# ControlBrickLogic2_0.net
KiCad netlist of a schematic drawn in Altium Designer
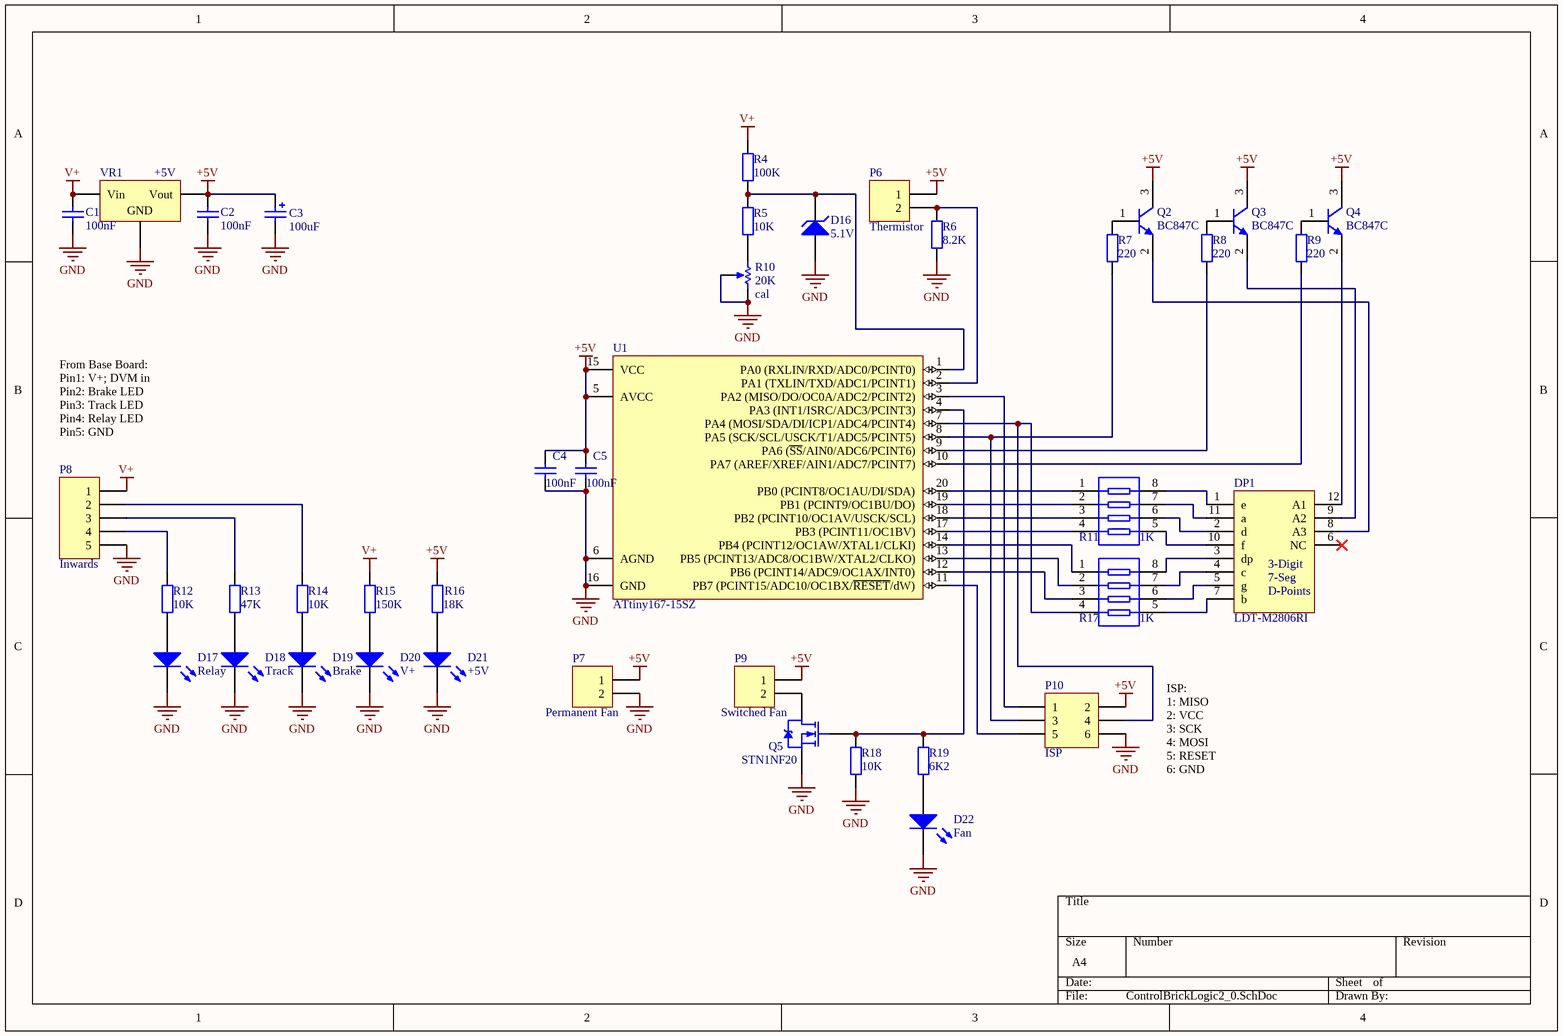
[diagram p0: ControlBrickLogic2_0.SchDoc]

(export (version "E")
  (design (tool "Eeschema 10.0.6"))
  (components
    (comp (ref "C1")
      (value "100nF")
      (footprint "1206")
      (description "Capacitor")
      (fields (field (name "Comment") "CapSMD") (field (name "PUBLISHER") "Altium Limited"))
      (libsource (lib "SpecificComponents") (part "CapSMD"))
    )
    (comp (ref "C2")
      (value "100nF")
      (footprint "1206")
      (description "Capacitor")
      (fields (field (name "Comment") "CapSMD") (field (name "PUBLISHER") "Altium Limited"))
      (libsource (lib "SpecificComponents") (part "CapSMD"))
    )
    (comp (ref "C3")
      (value "100uF")
      (footprint "SMDcap 5mm")
      (description "Polarized Capacitor (Axial)")
      (fields (field (name "Comment") "Supercap") (field (name "PUBLISHER") "Altium Limited"))
      (libsource (lib "Miscellaneous Devices") (part "Cap Pol2"))
    )
    (comp (ref "C4")
      (value "100nF")
      (footprint "1206")
      (description "Capacitor")
      (fields (field (name "Comment") "CapSMD") (field (name "PUBLISHER") "Altium Limited"))
      (libsource (lib "SpecificComponents") (part "CapSMD"))
    )
    (comp (ref "C5")
      (value "100nF")
      (footprint "1206")
      (description "Capacitor")
      (fields (field (name "Comment") "CapSMD") (field (name "PUBLISHER") "Altium Limited"))
      (libsource (lib "SpecificComponents") (part "CapSMD"))
    )
    (comp (ref "D16")
      (value "5.1V")
      (footprint "MiniMELF")
      (description "Zener Diode")
      (fields (field (name "PUBLISHER") "Altium Limited"))
      (libsource (lib "SpecificComponents") (part "D Zener"))
    )
    (comp (ref "D17")
      (value "Relay")
      (footprint "LED 2.54")
      (description "Typical RED GaAs LED")
      (fields (field (name "PUBLISHER") "Altium Limited"))
      (libsource (lib "Miscellaneous Devices") (part "LED1"))
    )
    (comp (ref "D18")
      (value "Track")
      (footprint "LED 2.54")
      (description "Typical RED GaAs LED")
      (fields (field (name "PUBLISHER") "Altium Limited"))
      (libsource (lib "Miscellaneous Devices") (part "LED1"))
    )
    (comp (ref "D19")
      (value "Brake")
      (footprint "LED 2.54")
      (description "Typical RED GaAs LED")
      (fields (field (name "PUBLISHER") "Altium Limited"))
      (libsource (lib "Miscellaneous Devices") (part "LED1"))
    )
    (comp (ref "D20")
      (value "V+")
      (footprint "LED 2.54")
      (description "Typical RED GaAs LED")
      (fields (field (name "PUBLISHER") "Altium Limited"))
      (libsource (lib "Miscellaneous Devices") (part "LED1"))
    )
    (comp (ref "D21")
      (value "+5V")
      (footprint "LED 2.54")
      (description "Typical RED GaAs LED")
      (fields (field (name "PUBLISHER") "Altium Limited"))
      (libsource (lib "Miscellaneous Devices") (part "LED1"))
    )
    (comp (ref "D22")
      (value "Fan")
      (footprint "LED 2.54")
      (description "Typical RED GaAs LED")
      (fields (field (name "PUBLISHER") "Altium Limited"))
      (libsource (lib "Miscellaneous Devices") (part "LED1"))
    )
    (comp (ref "DP1")
      (value "LDT-M2806RI")
      (footprint "LDT-M2806RI")
      (libsource (lib "SpecificComponents") (part "7Seg"))
    )
    (comp (ref "P6")
      (value "Thermistor")
      (footprint "HDR1X2")
      (description "Header, 2-Pin")
      (fields (field (name "PUBLISHER") "Altium Limited"))
      (libsource (lib "Miscellaneous Connectors") (part "Header 2"))
    )
    (comp (ref "P7")
      (value "Permanent Fan")
      (footprint "HDR1X2")
      (description "Header, 2-Pin")
      (fields (field (name "PUBLISHER") "Altium Limited"))
      (libsource (lib "Miscellaneous Connectors") (part "Header 2"))
    )
    (comp (ref "P8")
      (value "Inwards")
      (footprint "HDR1X5")
      (description "Header, 5-Pin")
      (fields (field (name "PUBLISHER") "Altium Limited"))
      (libsource (lib "Miscellaneous Connectors") (part "Header 5"))
    )
    (comp (ref "P9")
      (value "Switched Fan")
      (footprint "HDR1X2")
      (description "Header, 2-Pin")
      (fields (field (name "PUBLISHER") "Altium Limited"))
      (libsource (lib "Miscellaneous Connectors") (part "Header 2"))
    )
    (comp (ref "P10")
      (value "ISP")
      (footprint "HDR2X3")
      (description "Header, 3-Pin, Dual row")
      (fields (field (name "PUBLISHER") "Altium Limited"))
      (libsource (lib "Miscellaneous Connectors") (part "Header 3X2"))
    )
    (comp (ref "Q2")
      (value "BC847C")
      (footprint "SOT23")
      (description "NPN General Purpose Amplifier")
      (fields (field (name "PUBLISHER") "Altium Limited"))
      (libsource (lib "SpecificComponents") (part "BC847C"))
    )
    (comp (ref "Q3")
      (value "BC847C")
      (footprint "SOT23")
      (description "NPN General Purpose Amplifier")
      (fields (field (name "PUBLISHER") "Altium Limited"))
      (libsource (lib "SpecificComponents") (part "BC847C"))
    )
    (comp (ref "Q4")
      (value "BC847C")
      (footprint "SOT23")
      (description "NPN General Purpose Amplifier")
      (fields (field (name "PUBLISHER") "Altium Limited"))
      (libsource (lib "SpecificComponents") (part "BC847C"))
    )
    (comp (ref "Q5")
      (value "STN1NF20")
      (footprint "SOT223")
      (description "N-Channel MOSFET, SOT223")
      (fields (field (name "PUBLISHER") "Altium Limited"))
      (libsource (lib "SpecificComponents") (part "STN1NF20"))
    )
    (comp (ref "R4")
      (value "100K")
      (footprint "1206")
      (description "Resistor")
      (fields (field (name "Comment") "ResSMD") (field (name "PUBLISHER") "Altium Limited"))
      (libsource (lib "SpecificComponents") (part "ResSMD"))
    )
    (comp (ref "R5")
      (value "10K")
      (footprint "1206")
      (description "Resistor")
      (fields (field (name "Comment") "ResSMD") (field (name "PUBLISHER") "Altium Limited"))
      (libsource (lib "SpecificComponents") (part "ResSMD"))
    )
    (comp (ref "R6")
      (value "8.2K")
      (footprint "1206")
      (description "Resistor")
      (fields (field (name "Comment") "ResSMD") (field (name "PUBLISHER") "Altium Limited"))
      (libsource (lib "SpecificComponents") (part "ResSMD"))
    )
    (comp (ref "R7")
      (value "220")
      (footprint "1206")
      (description "Resistor")
      (fields (field (name "Comment") "ResSMD") (field (name "PUBLISHER") "Altium Limited"))
      (libsource (lib "SpecificComponents") (part "ResSMD"))
    )
    (comp (ref "R8")
      (value "220")
      (footprint "1206")
      (description "Resistor")
      (fields (field (name "Comment") "ResSMD") (field (name "PUBLISHER") "Altium Limited"))
      (libsource (lib "SpecificComponents") (part "ResSMD"))
    )
    (comp (ref "R9")
      (value "220")
      (footprint "1206")
      (description "Resistor")
      (fields (field (name "Comment") "ResSMD") (field (name "PUBLISHER") "Altium Limited"))
      (libsource (lib "SpecificComponents") (part "ResSMD"))
    )
    (comp (ref "R10")
      (value "cal")
      (footprint "Tr3296P")
      (description "Potentiometer")
      (fields (field (name "ALTIUM_VALUE") "20K") (field (name "PUBLISHER") "Altium Limited"))
      (libsource (lib "Miscellaneous Devices") (part "RPot"))
    )
    (comp (ref "R11")
      (value "1K")
      (footprint "ResNet1206_8")
      (description "Isolated Resistor Network")
      (libsource (lib "SpecificComponents") (part "ResNet4"))
    )
    (comp (ref "R12")
      (value "10K")
      (footprint "1206")
      (description "Resistor")
      (fields (field (name "Comment") "ResSMD") (field (name "PUBLISHER") "Altium Limited"))
      (libsource (lib "SpecificComponents") (part "ResSMD"))
    )
    (comp (ref "R13")
      (value "47K")
      (footprint "1206")
      (description "Resistor")
      (fields (field (name "Comment") "ResSMD") (field (name "PUBLISHER") "Altium Limited"))
      (libsource (lib "SpecificComponents") (part "ResSMD"))
    )
    (comp (ref "R14")
      (value "10K")
      (footprint "1206")
      (description "Resistor")
      (fields (field (name "Comment") "ResSMD") (field (name "PUBLISHER") "Altium Limited"))
      (libsource (lib "SpecificComponents") (part "ResSMD"))
    )
    (comp (ref "R15")
      (value "150K")
      (footprint "1206")
      (description "Resistor")
      (fields (field (name "Comment") "ResSMD") (field (name "PUBLISHER") "Altium Limited"))
      (libsource (lib "SpecificComponents") (part "ResSMD"))
    )
    (comp (ref "R16")
      (value "18K")
      (footprint "1206")
      (description "Resistor")
      (fields (field (name "Comment") "ResSMD") (field (name "PUBLISHER") "Altium Limited"))
      (libsource (lib "SpecificComponents") (part "ResSMD"))
    )
    (comp (ref "R17")
      (value "1K")
      (footprint "ResNet1206_8")
      (description "Isolated Resistor Network")
      (libsource (lib "SpecificComponents") (part "ResNet4"))
    )
    (comp (ref "R18")
      (value "10K")
      (footprint "1206")
      (description "Resistor")
      (fields (field (name "Comment") "ResSMD") (field (name "PUBLISHER") "Altium Limited"))
      (libsource (lib "SpecificComponents") (part "ResSMD"))
    )
    (comp (ref "R19")
      (value "6K2")
      (footprint "1206")
      (description "Resistor")
      (fields (field (name "Comment") "ResSMD") (field (name "PUBLISHER") "Altium Limited"))
      (libsource (lib "SpecificComponents") (part "ResSMD"))
    )
    (comp (ref "U1")
      (value "ATtiny167-15SZ")
      (footprint "20TG_N")
      (fields (field (name "PUBLISHER") "Altium Limited"))
      (libsource (lib "Atmel Microcontroller 8-Bit Automotive AVR") (part "ATtiny167-15SZ"))
    )
    (comp (ref "VR1")
      (value "+5V")
      (footprint "DPAK")
      (description "Voltage Regulator")
      (fields (field (name "PUBLISHER") "Altium Limited"))
      (libsource (lib "SpecificComponents") (part "Volt Reg"))
    )
  )
  (nets
    (net (code "1") (name "+5V") (class "Default")
      (node (ref "C2") (pin "2") (pinfunction "2_2") (pintype "passive"))
      (node (ref "C3") (pin "1") (pinfunction "1_1") (pintype "passive"))
      (node (ref "C4") (pin "2") (pinfunction "2_2") (pintype "passive"))
      (node (ref "C5") (pin "2") (pinfunction "2_2") (pintype "passive"))
      (node (ref "P10") (pin "2") (pinfunction "2_2") (pintype "passive"))
      (node (ref "P6") (pin "1") (pinfunction "1_1") (pintype "passive"))
      (node (ref "P7") (pin "1") (pinfunction "1_1") (pintype "passive"))
      (node (ref "P9") (pin "1") (pinfunction "1_1") (pintype "passive"))
      (node (ref "Q2") (pin "3") (pinfunction "C_3") (pintype "passive"))
      (node (ref "Q3") (pin "3") (pinfunction "C_3") (pintype "passive"))
      (node (ref "Q4") (pin "3") (pinfunction "C_3") (pintype "passive"))
      (node (ref "R16") (pin "2") (pinfunction "2_2") (pintype "passive"))
      (node (ref "U1") (pin "15") (pinfunction "VCC_15") (pintype "power_in"))
      (node (ref "U1") (pin "5") (pinfunction "AVCC_5") (pintype "power_in"))
      (node (ref "VR1") (pin "3") (pinfunction "Vout_3") (pintype "passive"))
    )
    (net (code "2") (name "GND") (class "Default")
      (node (ref "C1") (pin "1") (pinfunction "1_1") (pintype "passive"))
      (node (ref "C2") (pin "1") (pinfunction "1_1") (pintype "passive"))
      (node (ref "C3") (pin "2") (pinfunction "2_2") (pintype "passive"))
      (node (ref "C4") (pin "1") (pinfunction "1_1") (pintype "passive"))
      (node (ref "C5") (pin "1") (pinfunction "1_1") (pintype "passive"))
      (node (ref "D16") (pin "1") (pinfunction "A_1") (pintype "passive"))
      (node (ref "D17") (pin "2") (pinfunction "K_2") (pintype "passive"))
      (node (ref "D18") (pin "2") (pinfunction "K_2") (pintype "passive"))
      (node (ref "D19") (pin "2") (pinfunction "K_2") (pintype "passive"))
      (node (ref "D20") (pin "2") (pinfunction "K_2") (pintype "passive"))
      (node (ref "D21") (pin "2") (pinfunction "K_2") (pintype "passive"))
      (node (ref "D22") (pin "2") (pinfunction "K_2") (pintype "passive"))
      (node (ref "P10") (pin "6") (pinfunction "6_6") (pintype "passive"))
      (node (ref "P7") (pin "2") (pinfunction "2_2") (pintype "passive"))
      (node (ref "P8") (pin "5") (pinfunction "5_5") (pintype "passive"))
      (node (ref "Q5") (pin "3") (pinfunction "S_3") (pintype "passive"))
      (node (ref "R10") (pin "2") (pinfunction "BOT_2") (pintype "passive"))
      (node (ref "R10") (pin "3") (pinfunction "TAP_3") (pintype "passive"))
      (node (ref "R18") (pin "1") (pinfunction "1_1") (pintype "passive"))
      (node (ref "R6") (pin "1") (pinfunction "1_1") (pintype "passive"))
      (node (ref "U1") (pin "16") (pinfunction "GND_16") (pintype "power_in"))
      (node (ref "U1") (pin "6") (pinfunction "AGND_6") (pintype "power_in"))
      (node (ref "VR1") (pin "2") (pinfunction "GND_2") (pintype "passive"))
    )
    (net (code "3") (name "Net-(D16-K)") (class "Default")
      (node (ref "D16") (pin "2") (pinfunction "K_2") (pintype "passive"))
      (node (ref "R4") (pin "1") (pinfunction "1_1") (pintype "passive"))
      (node (ref "R5") (pin "2") (pinfunction "2_2") (pintype "passive"))
      (node (ref "U1") (pin "1") (pinfunction "PA0_(RXLIN/RXD/ADC0/PCINT0)_1") (pintype "bidirectional"))
    )
    (net (code "4") (name "Net-(D17-A)") (class "Default")
      (node (ref "D17") (pin "1") (pinfunction "A_1") (pintype "passive"))
      (node (ref "R12") (pin "1") (pinfunction "1_1") (pintype "passive"))
    )
    (net (code "5") (name "Net-(D18-A)") (class "Default")
      (node (ref "D18") (pin "1") (pinfunction "A_1") (pintype "passive"))
      (node (ref "R13") (pin "1") (pinfunction "1_1") (pintype "passive"))
    )
    (net (code "6") (name "Net-(D19-A)") (class "Default")
      (node (ref "D19") (pin "1") (pinfunction "A_1") (pintype "passive"))
      (node (ref "R14") (pin "1") (pinfunction "1_1") (pintype "passive"))
    )
    (net (code "7") (name "Net-(D20-A)") (class "Default")
      (node (ref "D20") (pin "1") (pinfunction "A_1") (pintype "passive"))
      (node (ref "R15") (pin "1") (pinfunction "1_1") (pintype "passive"))
    )
    (net (code "8") (name "Net-(D21-A)") (class "Default")
      (node (ref "D21") (pin "1") (pinfunction "A_1") (pintype "passive"))
      (node (ref "R16") (pin "1") (pinfunction "1_1") (pintype "passive"))
    )
    (net (code "9") (name "Net-(D22-A)") (class "Default")
      (node (ref "D22") (pin "1") (pinfunction "A_1") (pintype "passive"))
      (node (ref "R19") (pin "1") (pinfunction "1_1") (pintype "passive"))
    )
    (net (code "10") (name "Net-(DP1-A1)") (class "Default")
      (node (ref "DP1") (pin "12") (pinfunction "A1_12") (pintype "passive"))
      (node (ref "Q4") (pin "2") (pinfunction "E_2") (pintype "passive"))
    )
    (net (code "11") (name "Net-(DP1-A2)") (class "Default")
      (node (ref "DP1") (pin "9") (pinfunction "A2_9") (pintype "passive"))
      (node (ref "Q3") (pin "2") (pinfunction "E_2") (pintype "passive"))
    )
    (net (code "12") (name "Net-(DP1-A3)") (class "Default")
      (node (ref "DP1") (pin "8") (pinfunction "A3_8") (pintype "passive"))
      (node (ref "Q2") (pin "2") (pinfunction "E_2") (pintype "passive"))
    )
    (net (code "13") (name "Net-(DP1-a)") (class "Default")
      (node (ref "DP1") (pin "11") (pinfunction "a_11") (pintype "passive"))
      (node (ref "R11") (pin "7") (pinfunction "7_7") (pintype "passive"))
    )
    (net (code "14") (name "Net-(DP1-b)") (class "Default")
      (node (ref "DP1") (pin "7") (pinfunction "b_7") (pintype "passive"))
      (node (ref "R17") (pin "5") (pinfunction "5_5") (pintype "passive"))
    )
    (net (code "15") (name "Net-(DP1-c)") (class "Default")
      (node (ref "DP1") (pin "4") (pinfunction "c_4") (pintype "passive"))
      (node (ref "R17") (pin "7") (pinfunction "7_7") (pintype "passive"))
    )
    (net (code "16") (name "Net-(DP1-d)") (class "Default")
      (node (ref "DP1") (pin "2") (pinfunction "d_2") (pintype "passive"))
      (node (ref "R11") (pin "6") (pinfunction "6_6") (pintype "passive"))
    )
    (net (code "17") (name "Net-(DP1-dp)") (class "Default")
      (node (ref "DP1") (pin "3") (pinfunction "dp_3") (pintype "passive"))
      (node (ref "R17") (pin "8") (pinfunction "8_8") (pintype "passive"))
    )
    (net (code "18") (name "Net-(DP1-e)") (class "Default")
      (node (ref "DP1") (pin "1") (pinfunction "e_1") (pintype "passive"))
      (node (ref "R11") (pin "8") (pinfunction "8_8") (pintype "passive"))
    )
    (net (code "19") (name "Net-(DP1-f)") (class "Default")
      (node (ref "DP1") (pin "10") (pinfunction "f_10") (pintype "passive"))
      (node (ref "R11") (pin "5") (pinfunction "5_5") (pintype "passive"))
    )
    (net (code "20") (name "Net-(DP1-g)") (class "Default")
      (node (ref "DP1") (pin "5") (pinfunction "g_5") (pintype "passive"))
      (node (ref "R17") (pin "6") (pinfunction "6_6") (pintype "passive"))
    )
    (net (code "21") (name "Net-(P8-Pad2)") (class "Default")
      (node (ref "P8") (pin "2") (pinfunction "2_2") (pintype "passive"))
      (node (ref "R14") (pin "2") (pinfunction "2_2") (pintype "passive"))
    )
    (net (code "22") (name "Net-(P8-Pad3)") (class "Default")
      (node (ref "P8") (pin "3") (pinfunction "3_3") (pintype "passive"))
      (node (ref "R13") (pin "2") (pinfunction "2_2") (pintype "passive"))
    )
    (net (code "23") (name "Net-(P8-Pad4)") (class "Default")
      (node (ref "P8") (pin "4") (pinfunction "4_4") (pintype "passive"))
      (node (ref "R12") (pin "2") (pinfunction "2_2") (pintype "passive"))
    )
    (net (code "24") (name "Net-(Q2-B)") (class "Default")
      (node (ref "Q2") (pin "1") (pinfunction "B_1") (pintype "passive"))
      (node (ref "R7") (pin "2") (pinfunction "2_2") (pintype "passive"))
    )
    (net (code "25") (name "Net-(Q3-B)") (class "Default")
      (node (ref "Q3") (pin "1") (pinfunction "B_1") (pintype "passive"))
      (node (ref "R8") (pin "2") (pinfunction "2_2") (pintype "passive"))
    )
    (net (code "26") (name "Net-(Q4-B)") (class "Default")
      (node (ref "Q4") (pin "1") (pinfunction "B_1") (pintype "passive"))
      (node (ref "R9") (pin "2") (pinfunction "2_2") (pintype "passive"))
    )
    (net (code "27") (name "Net-(Q5-D)") (class "Default")
      (node (ref "P9") (pin "2") (pinfunction "2_2") (pintype "passive"))
      (node (ref "Q5") (pin "2") (pinfunction "D_2") (pintype "passive"))
    )
    (net (code "28") (name "Net-(Q5-G)") (class "Default")
      (node (ref "Q5") (pin "1") (pinfunction "G_1") (pintype "passive"))
      (node (ref "R18") (pin "2") (pinfunction "2_2") (pintype "passive"))
      (node (ref "R19") (pin "2") (pinfunction "2_2") (pintype "passive"))
      (node (ref "U1") (pin "4") (pinfunction "PA3_(INT1/ISRC/ADC3/PCINT3)_4") (pintype "bidirectional"))
    )
    (net (code "29") (name "Net-(R10-TOP)") (class "Default")
      (node (ref "R10") (pin "1") (pinfunction "TOP_1") (pintype "passive"))
      (node (ref "R5") (pin "1") (pinfunction "1_1") (pintype "passive"))
    )
    (net (code "30") (name "Net-(U1-PA1_(TXLIN{slash}TXD{slash}ADC1{slash}PCINT1))") (class "Default")
      (node (ref "P6") (pin "2") (pinfunction "2_2") (pintype "passive"))
      (node (ref "R6") (pin "2") (pinfunction "2_2") (pintype "passive"))
      (node (ref "U1") (pin "2") (pinfunction "PA1_(TXLIN/TXD/ADC1/PCINT1)_2") (pintype "bidirectional"))
    )
    (net (code "31") (name "Net-(U1-PA2_(MISO{slash}DO{slash}OC0A{slash}ADC2{slash}PCINT2))") (class "Default")
      (node (ref "P10") (pin "1") (pinfunction "1_1") (pintype "passive"))
      (node (ref "U1") (pin "3") (pinfunction "PA2_(MISO/DO/OC0A/ADC2/PCINT2)_3") (pintype "bidirectional"))
    )
    (net (code "32") (name "Net-(U1-PA4_(MOSI{slash}SDA{slash}DI{slash}ICP1{slash}ADC4{slash}PCINT4))") (class "Default")
      (node (ref "P10") (pin "4") (pinfunction "4_4") (pintype "passive"))
      (node (ref "R17") (pin "4") (pinfunction "4_4") (pintype "passive"))
      (node (ref "U1") (pin "7") (pinfunction "PA4_(MOSI/SDA/DI/ICP1/ADC4/PCINT4)_7") (pintype "bidirectional"))
    )
    (net (code "33") (name "Net-(U1-PA5_(SCK{slash}SCL{slash}USCK{slash}T1{slash}ADC5{slash}PCINT5))") (class "Default")
      (node (ref "P10") (pin "3") (pinfunction "3_3") (pintype "passive"))
      (node (ref "R7") (pin "1") (pinfunction "1_1") (pintype "passive"))
      (node (ref "U1") (pin "8") (pinfunction "PA5_(SCK/SCL/USCK/T1/ADC5/PCINT5)_8") (pintype "bidirectional"))
    )
    (net (code "34") (name "Net-(U1-PA6_(~{SS}{slash}AIN0{slash}ADC6{slash}PCINT6))") (class "Default")
      (node (ref "R8") (pin "1") (pinfunction "1_1") (pintype "passive"))
      (node (ref "U1") (pin "9") (pinfunction "PA6_(~{SS}/AIN0/ADC6/PCINT6)_9") (pintype "bidirectional"))
    )
    (net (code "35") (name "Net-(U1-PA7_(AREF{slash}XREF{slash}AIN1{slash}ADC7{slash}PCINT7))") (class "Default")
      (node (ref "R9") (pin "1") (pinfunction "1_1") (pintype "passive"))
      (node (ref "U1") (pin "10") (pinfunction "PA7_(AREF/XREF/AIN1/ADC7/PCINT7)_10") (pintype "bidirectional"))
    )
    (net (code "36") (name "Net-(U1-PB0_(PCINT8{slash}OC1AU{slash}DI{slash}SDA))") (class "Default")
      (node (ref "R11") (pin "1") (pinfunction "1_1") (pintype "passive"))
      (node (ref "U1") (pin "20") (pinfunction "PB0_(PCINT8/OC1AU/DI/SDA)_20") (pintype "bidirectional"))
    )
    (net (code "37") (name "Net-(U1-PB1_(PCINT9{slash}OC1BU{slash}DO))") (class "Default")
      (node (ref "R11") (pin "2") (pinfunction "2_2") (pintype "passive"))
      (node (ref "U1") (pin "19") (pinfunction "PB1_(PCINT9/OC1BU/DO)_19") (pintype "bidirectional"))
    )
    (net (code "38") (name "Net-(U1-PB2_(PCINT10{slash}OC1AV{slash}USCK{slash}SCL))") (class "Default")
      (node (ref "R11") (pin "3") (pinfunction "3_3") (pintype "passive"))
      (node (ref "U1") (pin "18") (pinfunction "PB2_(PCINT10/OC1AV/USCK/SCL)_18") (pintype "bidirectional"))
    )
    (net (code "39") (name "Net-(U1-PB3_(PCINT11{slash}OC1BV))") (class "Default")
      (node (ref "R11") (pin "4") (pinfunction "4_4") (pintype "passive"))
      (node (ref "U1") (pin "17") (pinfunction "PB3_(PCINT11/OC1BV)_17") (pintype "bidirectional"))
    )
    (net (code "40") (name "Net-(U1-PB4_(PCINT12{slash}OC1AW{slash}XTAL1{slash}CLKI))") (class "Default")
      (node (ref "R17") (pin "1") (pinfunction "1_1") (pintype "passive"))
      (node (ref "U1") (pin "14") (pinfunction "PB4_(PCINT12/OC1AW/XTAL1/CLKI)_14") (pintype "bidirectional"))
    )
    (net (code "41") (name "Net-(U1-PB5_(PCINT13{slash}ADC8{slash}OC1BW{slash}XTAL2{slash}CLKO))") (class "Default")
      (node (ref "R17") (pin "2") (pinfunction "2_2") (pintype "passive"))
      (node (ref "U1") (pin "13") (pinfunction "PB5_(PCINT13/ADC8/OC1BW/XTAL2/CLKO)_13") (pintype "bidirectional"))
    )
    (net (code "42") (name "Net-(U1-PB6_(PCINT14{slash}ADC9{slash}OC1AX{slash}INT0))") (class "Default")
      (node (ref "R17") (pin "3") (pinfunction "3_3") (pintype "passive"))
      (node (ref "U1") (pin "12") (pinfunction "PB6_(PCINT14/ADC9/OC1AX/INT0)_12") (pintype "bidirectional"))
    )
    (net (code "43") (name "Net-(U1-PB7_(PCINT15{slash}ADC10{slash}OC1BX{slash}~{RESET}{slash}dW))") (class "Default")
      (node (ref "P10") (pin "5") (pinfunction "5_5") (pintype "passive"))
      (node (ref "U1") (pin "11") (pinfunction "PB7_(PCINT15/ADC10/OC1BX/~{RESET}/dW)_11") (pintype "bidirectional"))
    )
    (net (code "44") (name "V+") (class "Default")
      (node (ref "C1") (pin "2") (pinfunction "2_2") (pintype "passive"))
      (node (ref "P8") (pin "1") (pinfunction "1_1") (pintype "passive"))
      (node (ref "R15") (pin "2") (pinfunction "2_2") (pintype "passive"))
      (node (ref "R4") (pin "2") (pinfunction "2_2") (pintype "passive"))
      (node (ref "VR1") (pin "1") (pinfunction "Vin_1") (pintype "passive"))
    )
    (net (code "45") (name "unconnected-(DP1-NC-Pad6)") (class "Default")
      (node (ref "DP1") (pin "6") (pinfunction "NC_6") (pintype "passive+no_connect"))
    )
  )
)
